# REDS_IO.net
KiCad netlist of a schematic drawn in Altium Designer
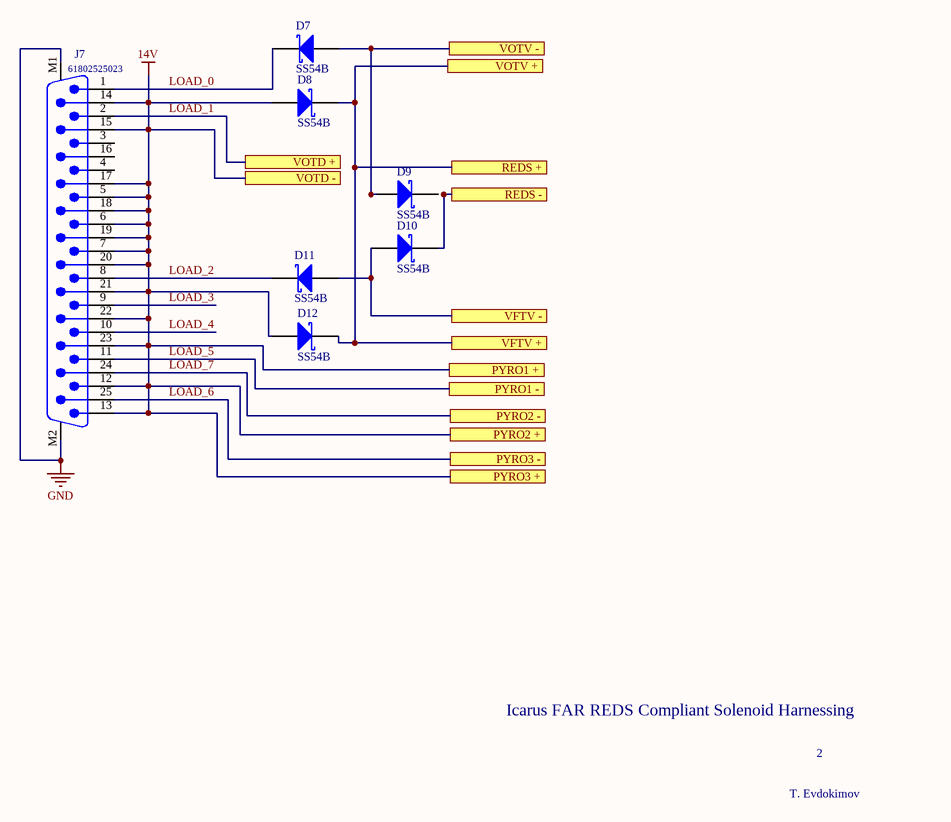
[diagram p0: REDS_IO.SchDoc]

(export (version "E")
  (design (tool "Eeschema 10.0.6"))
  (components
    (comp (ref "D7")
      (value "SS54B")
      (footprint "JCET-SMB-2_M")
      (description "Schottky Barrier Rectifier, 40 V, 5 A, -55 to 150 degC, 2-Pin SMD")
      (fields (field (name "MANUFACTURER") "JCET"))
      (libsource (lib "Boston University") (part "DSKY-AK-2"))
    )
    (comp (ref "D8")
      (value "SS54B")
      (footprint "JCET-SMB-2_M")
      (description "Schottky Barrier Rectifier, 40 V, 5 A, -55 to 150 degC, 2-Pin SMD")
      (fields (field (name "MANUFACTURER") "JCET"))
      (libsource (lib "Boston University") (part "DSKY-AK-2"))
    )
    (comp (ref "D9")
      (value "SS54B")
      (footprint "JCET-SMB-2_M")
      (description "Schottky Barrier Rectifier, 40 V, 5 A, -55 to 150 degC, 2-Pin SMD")
      (fields (field (name "MANUFACTURER") "JCET"))
      (libsource (lib "Boston University") (part "DSKY-AK-2"))
    )
    (comp (ref "D10")
      (value "SS54B")
      (footprint "JCET-SMB-2_M")
      (description "Schottky Barrier Rectifier, 40 V, 5 A, -55 to 150 degC, 2-Pin SMD")
      (fields (field (name "MANUFACTURER") "JCET"))
      (libsource (lib "Boston University") (part "DSKY-AK-2"))
    )
    (comp (ref "D11")
      (value "SS54B")
      (footprint "JCET-SMB-2_M")
      (description "Schottky Barrier Rectifier, 40 V, 5 A, -55 to 150 degC, 2-Pin SMD")
      (fields (field (name "MANUFACTURER") "JCET"))
      (libsource (lib "Boston University") (part "DSKY-AK-2"))
    )
    (comp (ref "D12")
      (value "SS54B")
      (footprint "JCET-SMB-2_M")
      (description "Schottky Barrier Rectifier, 40 V, 5 A, -55 to 150 degC, 2-Pin SMD")
      (fields (field (name "MANUFACTURER") "JCET"))
      (libsource (lib "Boston University") (part "DSKY-AK-2"))
    )
    (comp (ref "J7")
      (value "61802525023")
      (footprint "61802525023")
      (description "Male PCB Connector WR-DSUB, Vertical, 25 pins")
      (fields (field (name "MANUFACTURER") "Wurth Elektronik") (field (name "PUBLISHER") "WurthElektronik"))
      (libsource (lib "Altium Content Vault") (part "WE-CN-2S-2M-D25"))
    )
  )
  (nets
    (net (code "1") (name "/LOAD_0") (class "Default")
      (node (ref "D7") (pin "2") (pinfunction "K_2") (pintype "passive"))
      (node (ref "J7") (pin "1") (pinfunction "1_1") (pintype "passive"))
    )
    (net (code "2") (name "/LOAD_1") (class "Default")
      (node (ref "J7") (pin "2") (pinfunction "2_2") (pintype "passive"))
    )
    (net (code "3") (name "/LOAD_2") (class "Default")
      (node (ref "D11") (pin "2") (pinfunction "K_2") (pintype "passive"))
      (node (ref "J7") (pin "8") (pinfunction "8_8") (pintype "passive"))
    )
    (net (code "4") (name "/LOAD_3") (class "Default")
      (node (ref "J7") (pin "9") (pinfunction "9_9") (pintype "passive"))
    )
    (net (code "5") (name "/LOAD_4") (class "Default")
      (node (ref "J7") (pin "10") (pinfunction "10_10") (pintype "passive"))
    )
    (net (code "6") (name "/LOAD_5") (class "Default")
      (node (ref "J7") (pin "11") (pinfunction "11_11") (pintype "passive"))
    )
    (net (code "7") (name "/LOAD_6") (class "Default")
      (node (ref "J7") (pin "25") (pinfunction "25_25") (pintype "passive"))
    )
    (net (code "8") (name "/LOAD_7") (class "Default")
      (node (ref "J7") (pin "24") (pinfunction "24_24") (pintype "passive"))
    )
    (net (code "9") (name "/REDS +") (class "Default")
      (node (ref "D12") (pin "2") (pinfunction "K_2") (pintype "passive"))
      (node (ref "D8") (pin "2") (pinfunction "K_2") (pintype "passive"))
    )
    (net (code "10") (name "/REDS -") (class "Default")
      (node (ref "D10") (pin "2") (pinfunction "K_2") (pintype "passive"))
    )
    (net (code "11") (name "/VFTV -") (class "Default")
      (node (ref "D10") (pin "1") (pinfunction "A_1") (pintype "passive"))
      (node (ref "D11") (pin "1") (pinfunction "A_1") (pintype "passive"))
    )
    (net (code "12") (name "/VOTV -") (class "Default")
      (node (ref "D7") (pin "1") (pinfunction "A_1") (pintype "passive"))
      (node (ref "D9") (pin "1") (pinfunction "A_1") (pintype "passive"))
    )
    (net (code "13") (name "14V") (class "Default")
      (node (ref "D12") (pin "1") (pinfunction "A_1") (pintype "passive"))
      (node (ref "D8") (pin "1") (pinfunction "A_1") (pintype "passive"))
      (node (ref "J7") (pin "12") (pinfunction "12_12") (pintype "passive"))
      (node (ref "J7") (pin "13") (pinfunction "13_13") (pintype "passive"))
      (node (ref "J7") (pin "14") (pinfunction "14_14") (pintype "passive"))
      (node (ref "J7") (pin "15") (pinfunction "15_15") (pintype "passive"))
      (node (ref "J7") (pin "17") (pinfunction "17_17") (pintype "passive"))
      (node (ref "J7") (pin "18") (pinfunction "18_18") (pintype "passive"))
      (node (ref "J7") (pin "19") (pinfunction "19_19") (pintype "passive"))
      (node (ref "J7") (pin "20") (pinfunction "20_20") (pintype "passive"))
      (node (ref "J7") (pin "21") (pinfunction "21_21") (pintype "passive"))
      (node (ref "J7") (pin "22") (pinfunction "22_22") (pintype "passive"))
      (node (ref "J7") (pin "23") (pinfunction "23_23") (pintype "passive"))
      (node (ref "J7") (pin "5") (pinfunction "5_5") (pintype "passive"))
      (node (ref "J7") (pin "6") (pinfunction "6_6") (pintype "passive"))
      (node (ref "J7") (pin "7") (pinfunction "7_7") (pintype "passive"))
    )
    (net (code "14") (name "GND") (class "Default")
      (node (ref "J7") (pin "M1") (pinfunction "M1_M1") (pintype "passive"))
      (node (ref "J7") (pin "M2") (pinfunction "M2_M2") (pintype "passive"))
    )
    (net (code "15") (name "unconnected-(D9-K-Pad2)") (class "Default")
      (node (ref "D9") (pin "2") (pinfunction "K_2") (pintype "passive"))
    )
    (net (code "16") (name "unconnected-(J7-Pad3)") (class "Default")
      (node (ref "J7") (pin "3") (pinfunction "3_3") (pintype "passive"))
    )
    (net (code "17") (name "unconnected-(J7-Pad4)") (class "Default")
      (node (ref "J7") (pin "4") (pinfunction "4_4") (pintype "passive"))
    )
    (net (code "18") (name "unconnected-(J7-Pad16)") (class "Default")
      (node (ref "J7") (pin "16") (pinfunction "16_16") (pintype "passive"))
    )
  )
)
